# schema.net
KiCad netlist of a schematic drawn in EAGLE
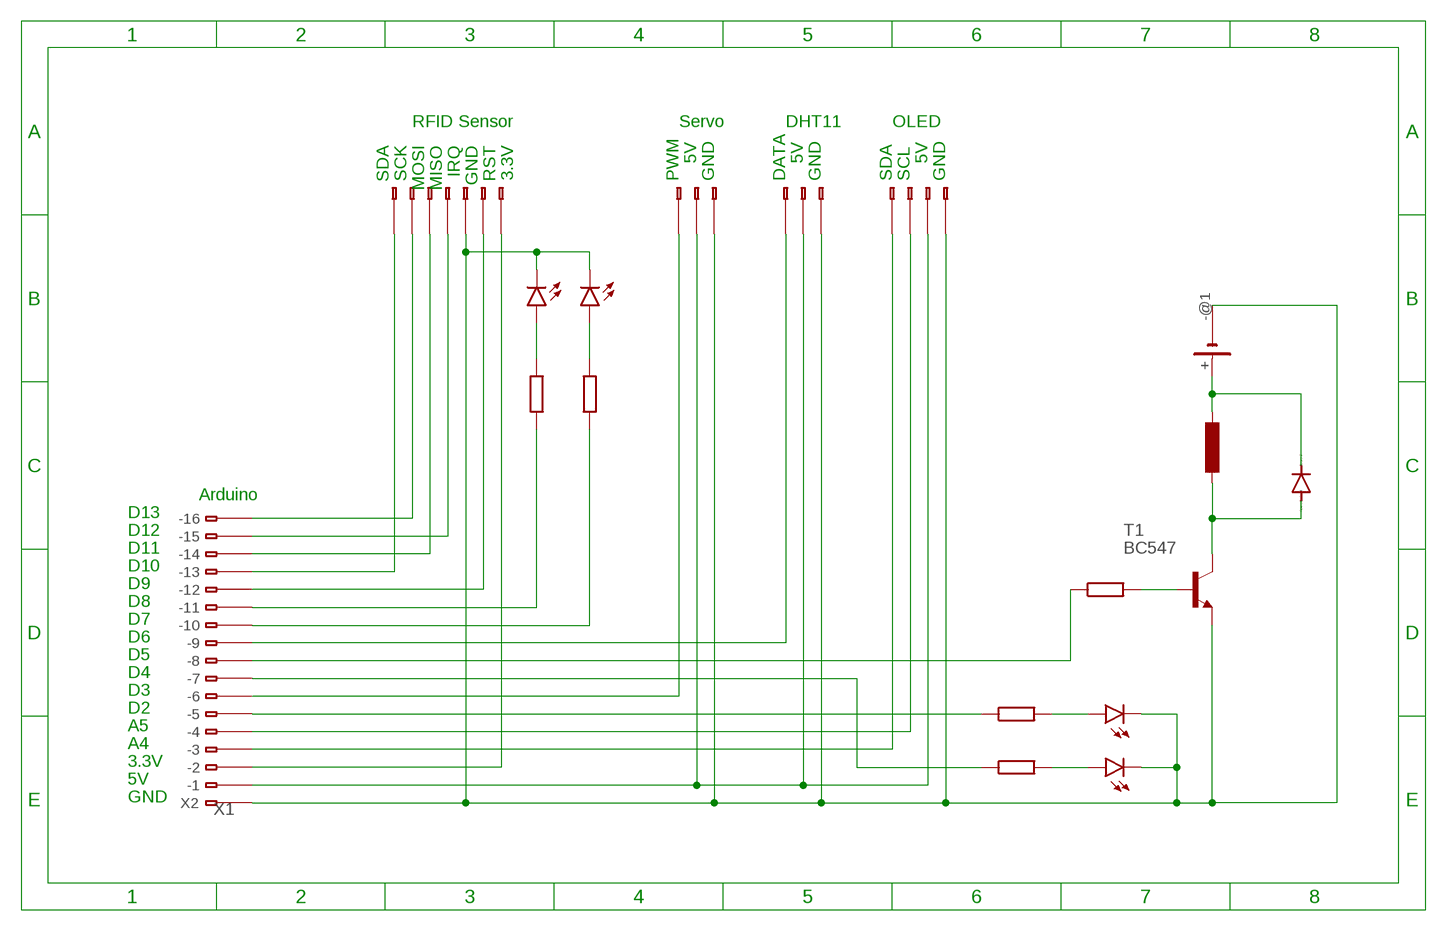
[diagram p0: schematic, sheet 1]

(export (version "E")
  (design (tool "Eeschema 10.0.6"))
  (components
    (comp (ref "D4")
      (value "1N4148DO35-7")
      (footprint "eagle-import:DO35-7")
      (libsource (lib "eagle-import") (part "1N4148DO35-7"))
    )
    (comp (ref "G1")
      (value "CR2/3")
      (footprint "eagle-import:CR2_3")
      (libsource (lib "eagle-import") (part "CR2/3"))
    )
    (comp (ref "LED1")
      (value "LED5MM")
      (footprint "eagle-import:LED5MM")
      (libsource (lib "eagle-import") (part "LED5MM"))
    )
    (comp (ref "LED2")
      (value "LED5MM")
      (footprint "eagle-import:LED5MM")
      (libsource (lib "eagle-import") (part "LED5MM"))
    )
    (comp (ref "LED3")
      (value "LED5MM")
      (footprint "eagle-import:LED5MM")
      (libsource (lib "eagle-import") (part "LED5MM"))
    )
    (comp (ref "LED4")
      (value "LED5MM")
      (footprint "eagle-import:LED5MM")
      (libsource (lib "eagle-import") (part "LED5MM"))
    )
    (comp (ref "T1")
      (value "BC547")
      (footprint "eagle-import:TO92")
      (libsource (lib "eagle-import") (part "BC547"))
    )
    (comp (ref "X1")
      (value "233-116")
      (footprint "eagle-import:233-116")
      (libsource (lib "eagle-import") (part "233-116"))
    )
    (comp (ref "X2")
      (value "WAGO1255-401-5")
      (footprint "eagle-import:255-401-5")
      (fields (field (name "MPN") "255-401"))
      (libsource (lib "eagle-import") (part "WAGO1255-401-5"))
    )
    (comp (ref "X3")
      (value "WAGO7-233-107")
      (footprint "eagle-import:233-107")
      (fields (field (name "MPN") "233-107"))
      (libsource (lib "eagle-import") (part "WAGO7-233-107"))
    )
    (comp (ref "X4")
      (value "WAGO3-233-103")
      (footprint "eagle-import:233-103")
      (fields (field (name "MPN") "233-103"))
      (libsource (lib "eagle-import") (part "WAGO3-233-103"))
    )
    (comp (ref "X5")
      (value "WAGO3-233-103")
      (footprint "eagle-import:233-103")
      (fields (field (name "MPN") "233-103"))
      (libsource (lib "eagle-import") (part "WAGO3-233-103"))
    )
    (comp (ref "X6")
      (value "WAGO4-233-104")
      (footprint "eagle-import:233-104")
      (fields (field (name "MPN") "233-104"))
      (libsource (lib "eagle-import") (part "WAGO4-233-104"))
    )
  )
  (nets
    (net (code "1") (name "Net-(D4-PadC)") (class "Default")
      (node (ref "D4") (pin "C") (pinfunction "C_C") (pintype "passive"))
      (node (ref "G1") (pin "+") (pinfunction "+_+") (pintype "passive"))
    )
    (net (code "2") (name "Net-(LED1-C)") (class "Default")
      (node (ref "G1") (pin "-@1") (pinfunction "-_-@1") (pintype "passive"))
      (node (ref "LED1") (pin "K") (pinfunction "C_K") (pintype "passive"))
      (node (ref "LED2") (pin "K") (pinfunction "C_K") (pintype "passive"))
      (node (ref "LED3") (pin "K") (pinfunction "C_K") (pintype "passive"))
      (node (ref "LED4") (pin "K") (pinfunction "C_K") (pintype "passive"))
      (node (ref "T1") (pin "1") (pinfunction "E_1") (pintype "passive"))
      (node (ref "X2") (pin "B1") (pinfunction "B1_B1") (pintype "passive"))
      (node (ref "X3") (pin "B5") (pinfunction "B1_B5") (pintype "passive"))
      (node (ref "X4") (pin "B3") (pinfunction "B1_B3") (pintype "passive"))
      (node (ref "X5") (pin "B3") (pinfunction "B1_B3") (pintype "passive"))
      (node (ref "X6") (pin "B4") (pinfunction "B1_B4") (pintype "passive"))
    )
    (net (code "3") (name "Net-(T1-C)") (class "Default")
      (node (ref "D4") (pin "A") (pinfunction "A_A") (pintype "passive"))
      (node (ref "T1") (pin "3") (pinfunction "C_3") (pintype "passive"))
    )
    (net (code "4") (name "Net-(X1-B-1)") (class "Default")
      (node (ref "X1") (pin "B1") (pinfunction "B-1_B1") (pintype "passive"))
      (node (ref "X4") (pin "B2") (pinfunction "B1_B2") (pintype "passive"))
      (node (ref "X5") (pin "B2") (pinfunction "B1_B2") (pintype "passive"))
      (node (ref "X6") (pin "B3") (pinfunction "B1_B3") (pintype "passive"))
    )
    (net (code "5") (name "Net-(X1-B-2)") (class "Default")
      (node (ref "X1") (pin "B2") (pinfunction "B-2_B2") (pintype "passive"))
      (node (ref "X3") (pin "B7") (pinfunction "B1_B7") (pintype "passive"))
    )
    (net (code "6") (name "Net-(X1-B-3)") (class "Default")
      (node (ref "X1") (pin "B3") (pinfunction "B-3_B3") (pintype "passive"))
      (node (ref "X6") (pin "B1") (pinfunction "B1_B1") (pintype "passive"))
    )
    (net (code "7") (name "Net-(X1-B-4)") (class "Default")
      (node (ref "X1") (pin "B4") (pinfunction "B-4_B4") (pintype "passive"))
      (node (ref "X6") (pin "B2") (pinfunction "B1_B2") (pintype "passive"))
    )
    (net (code "8") (name "Net-(X1-B-6)") (class "Default")
      (node (ref "X1") (pin "B6") (pinfunction "B-6_B6") (pintype "passive"))
      (node (ref "X4") (pin "B1") (pinfunction "B1_B1") (pintype "passive"))
    )
    (net (code "9") (name "Net-(X1-B-9)") (class "Default")
      (node (ref "X1") (pin "B9") (pinfunction "B-9_B9") (pintype "passive"))
      (node (ref "X5") (pin "B1") (pinfunction "B1_B1") (pintype "passive"))
    )
    (net (code "10") (name "Net-(X1-B-12)") (class "Default")
      (node (ref "X1") (pin "B12") (pinfunction "B-12_B12") (pintype "passive"))
      (node (ref "X3") (pin "B6") (pinfunction "B1_B6") (pintype "passive"))
    )
    (net (code "11") (name "Net-(X1-B-13)") (class "Default")
      (node (ref "X1") (pin "B13") (pinfunction "B-13_B13") (pintype "passive"))
      (node (ref "X3") (pin "B1") (pinfunction "B1_B1") (pintype "passive"))
    )
    (net (code "12") (name "Net-(X1-B-14)") (class "Default")
      (node (ref "X1") (pin "B14") (pinfunction "B-14_B14") (pintype "passive"))
      (node (ref "X3") (pin "B3") (pinfunction "B1_B3") (pintype "passive"))
    )
    (net (code "13") (name "Net-(X1-B-15)") (class "Default")
      (node (ref "X1") (pin "B15") (pinfunction "B-15_B15") (pintype "passive"))
      (node (ref "X3") (pin "B4") (pinfunction "B1_B4") (pintype "passive"))
    )
    (net (code "14") (name "Net-(X1-B-16)") (class "Default")
      (node (ref "X1") (pin "B16") (pinfunction "B-16_B16") (pintype "passive"))
      (node (ref "X3") (pin "B2") (pinfunction "B1_B2") (pintype "passive"))
    )
    (net (code "15") (name "unconnected-(G1---Pad-@2)") (class "Default")
      (node (ref "G1") (pin "-@2") (pinfunction "-_-@2") (pintype "passive"))
    )
    (net (code "16") (name "unconnected-(LED1-PadA)") (class "Default")
      (node (ref "LED1") (pin "A") (pinfunction "A_A") (pintype "passive"))
    )
    (net (code "17") (name "unconnected-(LED2-PadA)") (class "Default")
      (node (ref "LED2") (pin "A") (pinfunction "A_A") (pintype "passive"))
    )
    (net (code "18") (name "unconnected-(LED3-PadA)") (class "Default")
      (node (ref "LED3") (pin "A") (pinfunction "A_A") (pintype "passive"))
    )
    (net (code "19") (name "unconnected-(LED4-PadA)") (class "Default")
      (node (ref "LED4") (pin "A") (pinfunction "A_A") (pintype "passive"))
    )
    (net (code "20") (name "unconnected-(T1-B-Pad2)") (class "Default")
      (node (ref "T1") (pin "2") (pinfunction "B_2") (pintype "passive"))
    )
    (net (code "21") (name "unconnected-(X1--1-PadA1)") (class "Default")
      (node (ref "X1") (pin "A1") (pinfunction "-1_A1") (pintype "passive"))
    )
    (net (code "22") (name "unconnected-(X1--2-PadA2)") (class "Default")
      (node (ref "X1") (pin "A2") (pinfunction "-2_A2") (pintype "passive"))
    )
    (net (code "23") (name "unconnected-(X1--3-PadA3)") (class "Default")
      (node (ref "X1") (pin "A3") (pinfunction "-3_A3") (pintype "passive"))
    )
    (net (code "24") (name "unconnected-(X1--4-PadA4)") (class "Default")
      (node (ref "X1") (pin "A4") (pinfunction "-4_A4") (pintype "passive"))
    )
    (net (code "25") (name "unconnected-(X1--5-PadA5)") (class "Default")
      (node (ref "X1") (pin "A5") (pinfunction "-5_A5") (pintype "passive"))
    )
    (net (code "26") (name "unconnected-(X1--6-PadA6)") (class "Default")
      (node (ref "X1") (pin "A6") (pinfunction "-6_A6") (pintype "passive"))
    )
    (net (code "27") (name "unconnected-(X1--7-PadA7)") (class "Default")
      (node (ref "X1") (pin "A7") (pinfunction "-7_A7") (pintype "passive"))
    )
    (net (code "28") (name "unconnected-(X1--8-PadA8)") (class "Default")
      (node (ref "X1") (pin "A8") (pinfunction "-8_A8") (pintype "passive"))
    )
    (net (code "29") (name "unconnected-(X1--9-PadA9)") (class "Default")
      (node (ref "X1") (pin "A9") (pinfunction "-9_A9") (pintype "passive"))
    )
    (net (code "30") (name "unconnected-(X1--10-PadA10)") (class "Default")
      (node (ref "X1") (pin "A10") (pinfunction "-10_A10") (pintype "passive"))
    )
    (net (code "31") (name "unconnected-(X1--11-PadA11)") (class "Default")
      (node (ref "X1") (pin "A11") (pinfunction "-11_A11") (pintype "passive"))
    )
    (net (code "32") (name "unconnected-(X1--12-PadA12)") (class "Default")
      (node (ref "X1") (pin "A12") (pinfunction "-12_A12") (pintype "passive"))
    )
    (net (code "33") (name "unconnected-(X1--13-PadA13)") (class "Default")
      (node (ref "X1") (pin "A13") (pinfunction "-13_A13") (pintype "passive"))
    )
    (net (code "34") (name "unconnected-(X1--14-PadA14)") (class "Default")
      (node (ref "X1") (pin "A14") (pinfunction "-14_A14") (pintype "passive"))
    )
    (net (code "35") (name "unconnected-(X1--15-PadA15)") (class "Default")
      (node (ref "X1") (pin "A15") (pinfunction "-15_A15") (pintype "passive"))
    )
    (net (code "36") (name "unconnected-(X1--16-PadA16)") (class "Default")
      (node (ref "X1") (pin "A16") (pinfunction "-16_A16") (pintype "passive"))
    )
    (net (code "37") (name "unconnected-(X1-B-5-PadB5)") (class "Default")
      (node (ref "X1") (pin "B5") (pinfunction "B-5_B5") (pintype "passive"))
    )
    (net (code "38") (name "unconnected-(X1-B-7-PadB7)") (class "Default")
      (node (ref "X1") (pin "B7") (pinfunction "B-7_B7") (pintype "passive"))
    )
    (net (code "39") (name "unconnected-(X1-B-8-PadB8)") (class "Default")
      (node (ref "X1") (pin "B8") (pinfunction "B-8_B8") (pintype "passive"))
    )
    (net (code "40") (name "unconnected-(X1-B-10-PadB10)") (class "Default")
      (node (ref "X1") (pin "B10") (pinfunction "B-10_B10") (pintype "passive"))
    )
    (net (code "41") (name "unconnected-(X1-B-11-PadB11)") (class "Default")
      (node (ref "X1") (pin "B11") (pinfunction "B-11_B11") (pintype "passive"))
    )
    (net (code "42") (name "unconnected-(X2-PadA1)") (class "Default")
      (node (ref "X2") (pin "A1") (pinfunction "A1_A1") (pintype "passive"))
    )
    (net (code "43") (name "unconnected-(X3-PadA1)") (class "Default")
      (node (ref "X3") (pin "A1") (pinfunction "A1_A1") (pintype "passive"))
    )
    (net (code "44") (name "unconnected-(X3B-A1-PadA2)") (class "Default")
      (node (ref "X3") (pin "A2") (pinfunction "A1_A2") (pintype "passive"))
    )
    (net (code "45") (name "unconnected-(X3C-A1-PadA3)") (class "Default")
      (node (ref "X3") (pin "A3") (pinfunction "A1_A3") (pintype "passive"))
    )
    (net (code "46") (name "unconnected-(X3D-A1-PadA4)") (class "Default")
      (node (ref "X3") (pin "A4") (pinfunction "A1_A4") (pintype "passive"))
    )
    (net (code "47") (name "unconnected-(X3E-A1-PadA5)") (class "Default")
      (node (ref "X3") (pin "A5") (pinfunction "A1_A5") (pintype "passive"))
    )
    (net (code "48") (name "unconnected-(X3F-A1-PadA6)") (class "Default")
      (node (ref "X3") (pin "A6") (pinfunction "A1_A6") (pintype "passive"))
    )
    (net (code "49") (name "unconnected-(X3G-A1-PadA7)") (class "Default")
      (node (ref "X3") (pin "A7") (pinfunction "A1_A7") (pintype "passive"))
    )
    (net (code "50") (name "unconnected-(X4-PadA1)") (class "Default")
      (node (ref "X4") (pin "A1") (pinfunction "A1_A1") (pintype "passive"))
    )
    (net (code "51") (name "unconnected-(X4B-A1-PadA2)") (class "Default")
      (node (ref "X4") (pin "A2") (pinfunction "A1_A2") (pintype "passive"))
    )
    (net (code "52") (name "unconnected-(X4C-A1-PadA3)") (class "Default")
      (node (ref "X4") (pin "A3") (pinfunction "A1_A3") (pintype "passive"))
    )
    (net (code "53") (name "unconnected-(X5-PadA1)") (class "Default")
      (node (ref "X5") (pin "A1") (pinfunction "A1_A1") (pintype "passive"))
    )
    (net (code "54") (name "unconnected-(X5B-A1-PadA2)") (class "Default")
      (node (ref "X5") (pin "A2") (pinfunction "A1_A2") (pintype "passive"))
    )
    (net (code "55") (name "unconnected-(X5C-A1-PadA3)") (class "Default")
      (node (ref "X5") (pin "A3") (pinfunction "A1_A3") (pintype "passive"))
    )
    (net (code "56") (name "unconnected-(X6-PadA1)") (class "Default")
      (node (ref "X6") (pin "A1") (pinfunction "A1_A1") (pintype "passive"))
    )
    (net (code "57") (name "unconnected-(X6B-A1-PadA2)") (class "Default")
      (node (ref "X6") (pin "A2") (pinfunction "A1_A2") (pintype "passive"))
    )
    (net (code "58") (name "unconnected-(X6C-A1-PadA3)") (class "Default")
      (node (ref "X6") (pin "A3") (pinfunction "A1_A3") (pintype "passive"))
    )
    (net (code "59") (name "unconnected-(X6D-A1-PadA4)") (class "Default")
      (node (ref "X6") (pin "A4") (pinfunction "A1_A4") (pintype "passive"))
    )
  )
)
